# dw-link-probe-V2.net
KiCad netlist of a schematic drawn in EAGLE
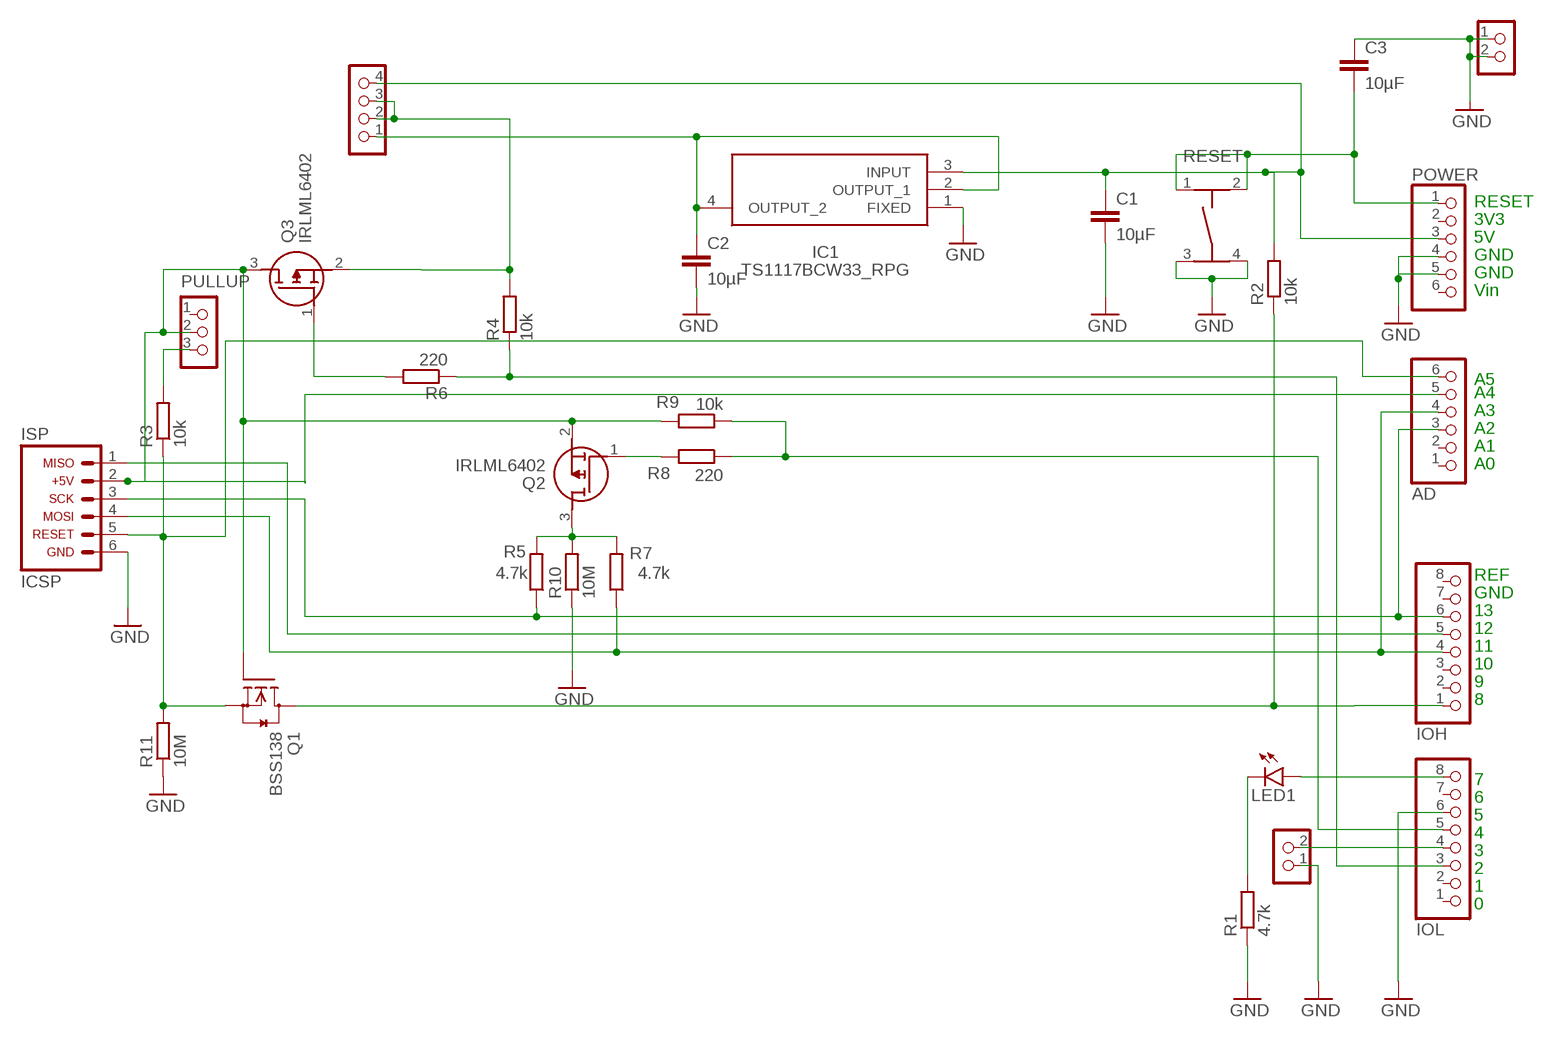
[diagram p0: schematic, sheet 1]

(export (version "E")
  (design (tool "Eeschema 10.0.6"))
  (components
    (comp (ref "AD")
      (value "PINHD-1X6")
      (footprint "eagle-import:1X06")
      (libsource (lib "eagle-import") (part "PINHD-1X6"))
    )
    (comp (ref "C1")
      (value "10µF")
      (footprint "eagle-import:C1206")
      (libsource (lib "eagle-import") (part "C-EUC1206"))
    )
    (comp (ref "C2")
      (value "10µF")
      (footprint "eagle-import:C1206")
      (libsource (lib "eagle-import") (part "C-EUC1206"))
    )
    (comp (ref "C3")
      (value "10µF")
      (footprint "eagle-import:C1206")
      (libsource (lib "eagle-import") (part "C-EUC1206"))
    )
    (comp (ref "DEBUG")
      (value "CON_HEADER_1X02-PTH")
      (footprint "eagle-import:M1X2")
      (libsource (lib "eagle-import") (part "CON_HEADER_1X02-PTH"))
    )
    (comp (ref "IC1")
      (value "TS1117BCW33_RPG")
      (footprint "eagle-import:SOT230P700X190-4N")
      (fields
        (field (name "ARROW_PART_NUMBER") "TS1117BCW33 RPG")
        (field (name "MOUSER_PART_NUMBER") "821-TS1117BCW33RPG")
      )
      (libsource (lib "eagle-import") (part "TS1117BCW33_RPG"))
    )
    (comp (ref "IOH")
      (value "PINHD-1X8")
      (footprint "eagle-import:1X08")
      (libsource (lib "eagle-import") (part "PINHD-1X8"))
    )
    (comp (ref "IOL")
      (value "PINHD-1X8")
      (footprint "eagle-import:1X08")
      (libsource (lib "eagle-import") (part "PINHD-1X8"))
    )
    (comp (ref "ISP")
      (value "ARDUINO_CONN-ICSP")
      (footprint "eagle-import:CONN-2X03")
      (libsource (lib "eagle-import") (part "ARDUINO_CONN-ICSP"))
    )
    (comp (ref "LED1")
      (value "LEDCHIPLED_1206")
      (footprint "eagle-import:CHIPLED_1206")
      (libsource (lib "eagle-import") (part "LEDCHIPLED_1206"))
    )
    (comp (ref "POWER")
      (value "PINHD-1X6")
      (footprint "eagle-import:1X06")
      (libsource (lib "eagle-import") (part "PINHD-1X6"))
    )
    (comp (ref "PULLUP")
      (value "CON_HEADER_1X03-PTH")
      (footprint "eagle-import:M1X3")
      (libsource (lib "eagle-import") (part "CON_HEADER_1X03-PTH"))
    )
    (comp (ref "Q1")
      (value "BSS138")
      (footprint "eagle-import:SOT23")
      (libsource (lib "eagle-import") (part "BSS138"))
    )
    (comp (ref "Q2")
      (value "IRLML6402")
      (footprint "eagle-import:SOT95P237X112-3N")
      (libsource (lib "eagle-import") (part "IRLML6402"))
    )
    (comp (ref "Q3")
      (value "IRLML6402")
      (footprint "eagle-import:SOT95P237X112-3N")
      (libsource (lib "eagle-import") (part "IRLML6402"))
    )
    (comp (ref "R1")
      (value "4.7k")
      (footprint "eagle-import:R1206")
      (libsource (lib "eagle-import") (part "R-EU_R1206"))
    )
    (comp (ref "R2")
      (value "10k")
      (footprint "eagle-import:R1206")
      (libsource (lib "eagle-import") (part "R-EU_R1206"))
    )
    (comp (ref "R3")
      (value "10k")
      (footprint "eagle-import:R1206")
      (libsource (lib "eagle-import") (part "R-EU_R1206"))
    )
    (comp (ref "R4")
      (value "10k")
      (footprint "eagle-import:R1206")
      (libsource (lib "eagle-import") (part "R-EU_R1206"))
    )
    (comp (ref "R5")
      (value "4.7k")
      (footprint "eagle-import:R1206")
      (libsource (lib "eagle-import") (part "R-EU_R1206"))
    )
    (comp (ref "R6")
      (value "220")
      (footprint "eagle-import:R1206")
      (libsource (lib "eagle-import") (part "R-EU_R1206"))
    )
    (comp (ref "R7")
      (value "4.7k")
      (footprint "eagle-import:R1206")
      (libsource (lib "eagle-import") (part "R-EU_R1206"))
    )
    (comp (ref "R8")
      (value "220")
      (footprint "eagle-import:R1206")
      (libsource (lib "eagle-import") (part "R-EU_R1206"))
    )
    (comp (ref "R9")
      (value "10k")
      (footprint "eagle-import:R1206")
      (libsource (lib "eagle-import") (part "R-EU_R1206"))
    )
    (comp (ref "R10")
      (value "10M")
      (footprint "eagle-import:R1206")
      (libsource (lib "eagle-import") (part "R-EU_R1206"))
    )
    (comp (ref "R11")
      (value "10M")
      (footprint "eagle-import:R1206")
      (libsource (lib "eagle-import") (part "R-EU_R1206"))
    )
    (comp (ref "RESDIS")
      (value "CON_HEADER_1X02-PTH")
      (footprint "eagle-import:M1X2")
      (libsource (lib "eagle-import") (part "CON_HEADER_1X02-PTH"))
    )
    (comp (ref "RESET")
      (value "TASTER-9314_SMD")
      (footprint "eagle-import:TASTER-9314_SMD")
      (libsource (lib "eagle-import") (part "TASTER-9314_SMD"))
    )
    (comp (ref "SUPPLY")
      (value "CON_HEADER_1X04")
      (footprint "eagle-import:M1X4")
      (libsource (lib "eagle-import") (part "CON_HEADER_1X04"))
    )
  )
  (nets
    (net (code "1") (name "GND") (class "Default")
      (node (ref "C1") (pin "2") (pinfunction "2_2") (pintype "passive"))
      (node (ref "C2") (pin "2") (pinfunction "2_2") (pintype "passive"))
      (node (ref "C3") (pin "1") (pinfunction "1_1") (pintype "passive"))
      (node (ref "DEBUG") (pin "1") (pinfunction "1_1") (pintype "passive"))
      (node (ref "IC1") (pin "1") (pinfunction "FIXED_1") (pintype "bidirectional"))
      (node (ref "IOL") (pin "6") (pinfunction "6_6") (pintype "passive"))
      (node (ref "ISP") (pin "6") (pinfunction "6_6") (pintype "passive"))
      (node (ref "POWER") (pin "4") (pinfunction "4_4") (pintype "passive"))
      (node (ref "POWER") (pin "5") (pinfunction "5_5") (pintype "passive"))
      (node (ref "R1") (pin "1") (pinfunction "1_1") (pintype "passive"))
      (node (ref "R10") (pin "1") (pinfunction "1_1") (pintype "passive"))
      (node (ref "R11") (pin "1") (pinfunction "1_1") (pintype "passive"))
      (node (ref "RESDIS") (pin "1") (pinfunction "1_1") (pintype "passive"))
      (node (ref "RESDIS") (pin "2") (pinfunction "2_2") (pintype "passive"))
      (node (ref "RESET") (pin "3") (pinfunction "3_3") (pintype "passive"))
      (node (ref "RESET") (pin "4") (pinfunction "4_4") (pintype "passive"))
    )
    (net (code "2") (name "Net-(AD-Pad3)") (class "Default")
      (node (ref "AD") (pin "3") (pinfunction "3_3") (pintype "passive"))
      (node (ref "IOH") (pin "6") (pinfunction "6_6") (pintype "passive"))
      (node (ref "ISP") (pin "3") (pinfunction "3_3") (pintype "passive"))
      (node (ref "R5") (pin "1") (pinfunction "1_1") (pintype "passive"))
    )
    (net (code "3") (name "Net-(AD-Pad4)") (class "Default")
      (node (ref "AD") (pin "4") (pinfunction "4_4") (pintype "passive"))
      (node (ref "IOH") (pin "4") (pinfunction "4_4") (pintype "passive"))
      (node (ref "ISP") (pin "4") (pinfunction "4_4") (pintype "passive"))
      (node (ref "R7") (pin "1") (pinfunction "1_1") (pintype "passive"))
    )
    (net (code "4") (name "Net-(C3-Pad2)") (class "Default")
      (node (ref "C3") (pin "2") (pinfunction "2_2") (pintype "passive"))
      (node (ref "POWER") (pin "1") (pinfunction "1_1") (pintype "passive"))
      (node (ref "RESET") (pin "1") (pinfunction "1_1") (pintype "passive"))
      (node (ref "RESET") (pin "2") (pinfunction "2_2") (pintype "passive"))
    )
    (net (code "5") (name "Net-(DEBUG-Pad2)") (class "Default")
      (node (ref "DEBUG") (pin "2") (pinfunction "2_2") (pintype "passive"))
      (node (ref "IOL") (pin "4") (pinfunction "4_4") (pintype "passive"))
    )
    (net (code "6") (name "Net-(IC1-INPUT)") (class "Default")
      (node (ref "C1") (pin "1") (pinfunction "1_1") (pintype "passive"))
      (node (ref "IC1") (pin "3") (pinfunction "INPUT_3") (pintype "bidirectional"))
      (node (ref "POWER") (pin "3") (pinfunction "3_3") (pintype "passive"))
      (node (ref "R2") (pin "2") (pinfunction "2_2") (pintype "passive"))
      (node (ref "SUPPLY") (pin "4") (pinfunction "4_4") (pintype "bidirectional"))
    )
    (net (code "7") (name "Net-(IC1-OUTPUT_1)") (class "Default")
      (node (ref "C2") (pin "1") (pinfunction "1_1") (pintype "passive"))
      (node (ref "IC1") (pin "2") (pinfunction "OUTPUT_1_2") (pintype "bidirectional"))
      (node (ref "IC1") (pin "4") (pinfunction "OUTPUT_2_4") (pintype "bidirectional"))
      (node (ref "SUPPLY") (pin "1") (pinfunction "1_1") (pintype "bidirectional"))
    )
    (net (code "8") (name "Net-(IOH-Pad5)") (class "Default")
      (node (ref "IOH") (pin "5") (pinfunction "5_5") (pintype "passive"))
      (node (ref "ISP") (pin "1") (pinfunction "1_1") (pintype "passive"))
    )
    (net (code "9") (name "Net-(IOL-Pad3)") (class "Default")
      (node (ref "IOL") (pin "3") (pinfunction "3_3") (pintype "passive"))
      (node (ref "R4") (pin "1") (pinfunction "1_1") (pintype "passive"))
      (node (ref "R6") (pin "1") (pinfunction "1_1") (pintype "passive"))
    )
    (net (code "10") (name "Net-(IOL-Pad5)") (class "Default")
      (node (ref "IOL") (pin "5") (pinfunction "5_5") (pintype "passive"))
      (node (ref "R8") (pin "1") (pinfunction "1_1") (pintype "passive"))
      (node (ref "R9") (pin "1") (pinfunction "1_1") (pintype "passive"))
    )
    (net (code "11") (name "Net-(IOL-Pad8)") (class "Default")
      (node (ref "IOL") (pin "8") (pinfunction "8_8") (pintype "passive"))
      (node (ref "LED1") (pin "A") (pinfunction "A_A") (pintype "passive"))
    )
    (net (code "12") (name "Net-(LED1-PadC)") (class "Default")
      (node (ref "LED1") (pin "C") (pinfunction "C_C") (pintype "passive"))
      (node (ref "R1") (pin "2") (pinfunction "2_2") (pintype "passive"))
    )
    (net (code "13") (name "Net-(PULLUP-Pad3)") (class "Default")
      (node (ref "PULLUP") (pin "3") (pinfunction "3_3") (pintype "bidirectional"))
      (node (ref "R3") (pin "2") (pinfunction "2_2") (pintype "passive"))
    )
    (net (code "14") (name "Net-(Q1-D)") (class "Default")
      (node (ref "IOH") (pin "1") (pinfunction "1_1") (pintype "passive"))
      (node (ref "Q1") (pin "3") (pinfunction "D_3") (pintype "passive"))
      (node (ref "R2") (pin "1") (pinfunction "1_1") (pintype "passive"))
    )
    (net (code "15") (name "Net-(Q1-G)") (class "Default")
      (node (ref "AD") (pin "5") (pinfunction "5_5") (pintype "passive"))
      (node (ref "ISP") (pin "2") (pinfunction "2_2") (pintype "passive"))
      (node (ref "PULLUP") (pin "2") (pinfunction "2_2") (pintype "bidirectional"))
      (node (ref "Q1") (pin "1") (pinfunction "G_1") (pintype "passive"))
      (node (ref "Q2") (pin "2") (pinfunction "S_2") (pintype "bidirectional"))
      (node (ref "Q3") (pin "3") (pinfunction "D_3") (pintype "bidirectional"))
      (node (ref "R9") (pin "2") (pinfunction "2_2") (pintype "passive"))
    )
    (net (code "16") (name "Net-(Q1-S)") (class "Default")
      (node (ref "AD") (pin "6") (pinfunction "6_6") (pintype "passive"))
      (node (ref "ISP") (pin "5") (pinfunction "5_5") (pintype "passive"))
      (node (ref "Q1") (pin "2") (pinfunction "S_2") (pintype "passive"))
      (node (ref "R11") (pin "2") (pinfunction "2_2") (pintype "passive"))
      (node (ref "R3") (pin "1") (pinfunction "1_1") (pintype "passive"))
    )
    (net (code "17") (name "Net-(Q2-D)") (class "Default")
      (node (ref "Q2") (pin "3") (pinfunction "D_3") (pintype "bidirectional"))
      (node (ref "R10") (pin "2") (pinfunction "2_2") (pintype "passive"))
      (node (ref "R5") (pin "2") (pinfunction "2_2") (pintype "passive"))
      (node (ref "R7") (pin "2") (pinfunction "2_2") (pintype "passive"))
    )
    (net (code "18") (name "Net-(Q2-G)") (class "Default")
      (node (ref "Q2") (pin "1") (pinfunction "G_1") (pintype "bidirectional"))
      (node (ref "R8") (pin "2") (pinfunction "2_2") (pintype "passive"))
    )
    (net (code "19") (name "Net-(Q3-G)") (class "Default")
      (node (ref "Q3") (pin "1") (pinfunction "G_1") (pintype "bidirectional"))
      (node (ref "R6") (pin "2") (pinfunction "2_2") (pintype "passive"))
    )
    (net (code "20") (name "Net-(Q3-S)") (class "Default")
      (node (ref "Q3") (pin "2") (pinfunction "S_2") (pintype "bidirectional"))
      (node (ref "R4") (pin "2") (pinfunction "2_2") (pintype "passive"))
      (node (ref "SUPPLY") (pin "2") (pinfunction "2_2") (pintype "bidirectional"))
      (node (ref "SUPPLY") (pin "3") (pinfunction "3_3") (pintype "bidirectional"))
    )
    (net (code "21") (name "unconnected-(AD-Pad1)") (class "Default")
      (node (ref "AD") (pin "1") (pinfunction "1_1") (pintype "passive"))
    )
    (net (code "22") (name "unconnected-(AD-Pad2)") (class "Default")
      (node (ref "AD") (pin "2") (pinfunction "2_2") (pintype "passive"))
    )
    (net (code "23") (name "unconnected-(IOH-Pad2)") (class "Default")
      (node (ref "IOH") (pin "2") (pinfunction "2_2") (pintype "passive"))
    )
    (net (code "24") (name "unconnected-(IOH-Pad3)") (class "Default")
      (node (ref "IOH") (pin "3") (pinfunction "3_3") (pintype "passive"))
    )
    (net (code "25") (name "unconnected-(IOH-Pad7)") (class "Default")
      (node (ref "IOH") (pin "7") (pinfunction "7_7") (pintype "passive"))
    )
    (net (code "26") (name "unconnected-(IOH-Pad8)") (class "Default")
      (node (ref "IOH") (pin "8") (pinfunction "8_8") (pintype "passive"))
    )
    (net (code "27") (name "unconnected-(IOL-Pad1)") (class "Default")
      (node (ref "IOL") (pin "1") (pinfunction "1_1") (pintype "passive"))
    )
    (net (code "28") (name "unconnected-(IOL-Pad2)") (class "Default")
      (node (ref "IOL") (pin "2") (pinfunction "2_2") (pintype "passive"))
    )
    (net (code "29") (name "unconnected-(IOL-Pad7)") (class "Default")
      (node (ref "IOL") (pin "7") (pinfunction "7_7") (pintype "passive"))
    )
    (net (code "30") (name "unconnected-(POWER-Pad2)") (class "Default")
      (node (ref "POWER") (pin "2") (pinfunction "2_2") (pintype "passive"))
    )
    (net (code "31") (name "unconnected-(POWER-Pad6)") (class "Default")
      (node (ref "POWER") (pin "6") (pinfunction "6_6") (pintype "passive"))
    )
    (net (code "32") (name "unconnected-(PULLUP-Pad1)") (class "Default")
      (node (ref "PULLUP") (pin "1") (pinfunction "1_1") (pintype "bidirectional"))
    )
  )
)
